# MIO_SD.net
KiCad netlist of a schematic drawn in Altium Designer
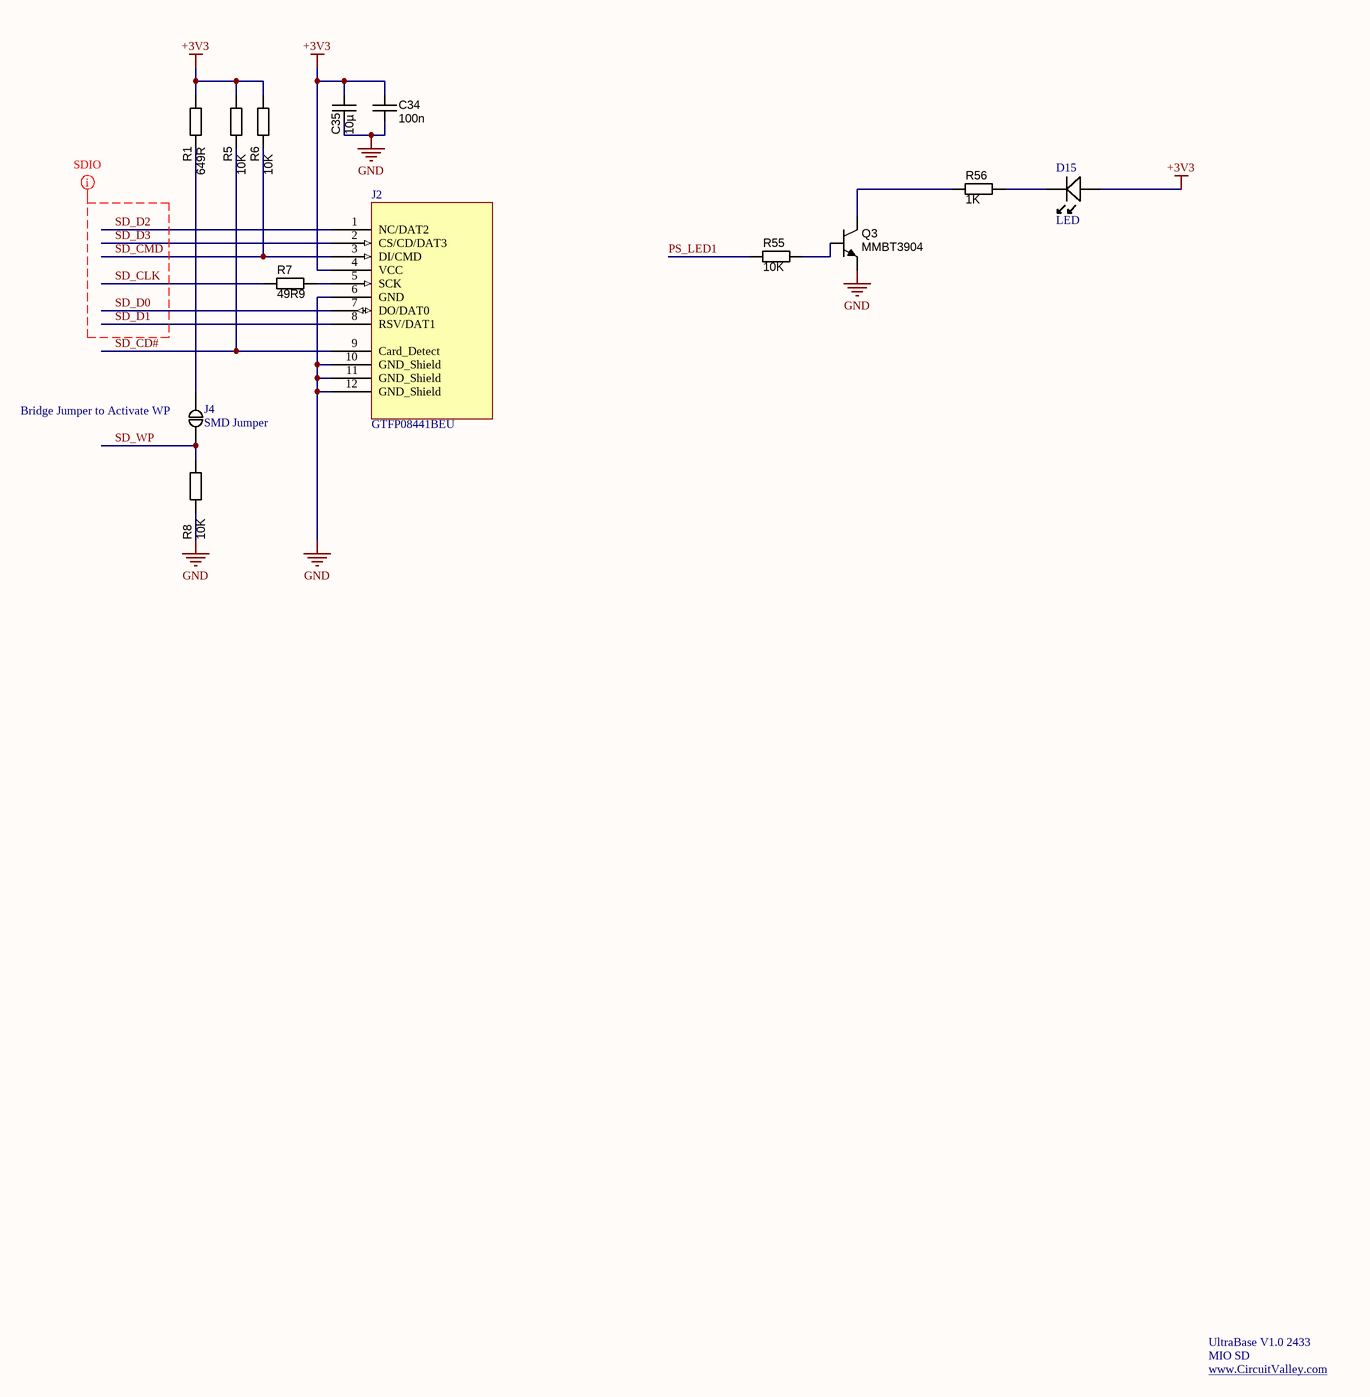
[diagram p0: MIO_SD.SchDoc]

(export (version "E")
  (design (tool "Eeschema 10.0.6"))
  (components
    (comp (ref "C34")
      (value "100n")
      (footprint "CAPC1608N")
      (description "Capacitor SMD Cer 1nF 10% 100V X7R 0603")
      (fields (field (name "TOLERANCE") "±10%"))
      (libsource (lib "PBL - Capacitors") (part "CAPC_1n_0603_100V"))
    )
    (comp (ref "C35")
      (value "10µ")
      (footprint "CAPC3225N")
      (description "Capacitor SMD Cer 10uF 20% 16V X5R 1210")
      (fields (field (name "TOLERANCE") "±20%"))
      (libsource (lib "PBL - Capacitors") (part "CAPC_10u_1210_50V"))
    )
    (comp (ref "D15") (value "LED") (footprint "1206_LED") (libsource (lib "cvlib") (part "LED")))
    (comp (ref "J2")
      (value "GTFP08441BEU")
      (footprint "GTFP08441BEU")
      (description "MicroSD card")
      (libsource (lib "cvlib") (part "GTFP08441BEU"))
    )
    (comp (ref "J4")
      (value "SMD Jumper")
      (footprint "SMD_Jumper")
      (libsource (lib "cvlib") (part "SMD_Jumper"))
    )
    (comp (ref "Q3")
      (value "NPN_MMBT3904")
      (footprint "SOT23-3")
      (description "Transistor SMD NPN 40V 0.2A 350mW SOT-23")
      (fields (field (name "MANUFACTURER PART NUMBER 1") "MMBT3904"))
      (libsource (lib "PBL - Transistors") (part "NPN_MMBT3904"))
    )
    (comp (ref "R1")
      (value "649R")
      (footprint "RESC1608N")
      (description "Resistor, SMD chip")
      (fields (field (name "TOLERANCE") "±5%") (field (name "Comment") "RES_NL_0603"))
      (libsource (lib "PBL - Resistors") (part "RES_NL_0603"))
    )
    (comp (ref "R5")
      (value "10K")
      (footprint "RESC1608N")
      (description "Resistor, SMD chip")
      (fields (field (name "TOLERANCE") "±5%") (field (name "Comment") "RES_NL_0603"))
      (libsource (lib "PBL - Resistors") (part "RES_NL_0603"))
    )
    (comp (ref "R6")
      (value "10K")
      (footprint "RESC1608N")
      (description "Resistor, SMD chip")
      (fields (field (name "TOLERANCE") "±5%") (field (name "Comment") "RES_NL_0603"))
      (libsource (lib "PBL - Resistors") (part "RES_NL_0603"))
    )
    (comp (ref "R7")
      (value "49R9")
      (footprint "RESC1608N")
      (description "Resistor, SMD chip")
      (fields (field (name "TOLERANCE") "±5%") (field (name "Comment") "RES_NL_0603"))
      (libsource (lib "") (part "RES_NL_0603_1"))
    )
    (comp (ref "R8")
      (value "10K")
      (footprint "RESC1608N")
      (description "Resistor, SMD chip")
      (fields (field (name "TOLERANCE") "±5%") (field (name "Comment") "RES_NL_0603"))
      (libsource (lib "PBL - Resistors") (part "RES_NL_0603"))
    )
    (comp (ref "R55")
      (value "10K")
      (footprint "RESC1608N")
      (description "Resistor, SMD chip")
      (fields (field (name "TOLERANCE") "±5%") (field (name "Comment") "RES_NL_0603"))
      (libsource (lib "") (part "RES_NL_0603_1"))
    )
    (comp (ref "R56")
      (value "1K")
      (footprint "RESC1608N")
      (description "Resistor, SMD chip")
      (fields (field (name "TOLERANCE") "±5%") (field (name "Comment") "RES_NL_0603"))
      (libsource (lib "") (part "RES_NL_0603_1"))
    )
  )
  (nets
    (net (code "1") (name "+3V3") (class "Default")
      (node (ref "C34") (pin "1") (pintype "passive"))
      (node (ref "C35") (pin "1") (pintype "passive"))
      (node (ref "D15") (pin "A") (pinfunction "A_A") (pintype "passive"))
      (node (ref "J2") (pin "4") (pinfunction "VCC_4") (pintype "power_in"))
      (node (ref "R1") (pin "1") (pinfunction "1_1") (pintype "passive"))
      (node (ref "R5") (pin "1") (pinfunction "1_1") (pintype "passive"))
      (node (ref "R6") (pin "1") (pinfunction "1_1") (pintype "passive"))
    )
    (net (code "2") (name "/PS_LED1") (class "Default")
      (node (ref "R55") (pin "1") (pinfunction "1_1") (pintype "passive"))
    )
    (net (code "3") (name "/SD_CD#") (class "Default")
      (node (ref "J2") (pin "9") (pinfunction "Card_Detect_9") (pintype "passive"))
      (node (ref "R5") (pin "2") (pinfunction "2_2") (pintype "passive"))
    )
    (net (code "4") (name "/SD_CLK") (class "Default")
      (node (ref "R7") (pin "1") (pinfunction "1_1") (pintype "passive"))
    )
    (net (code "5") (name "/SD_CMD") (class "Default")
      (node (ref "J2") (pin "3") (pinfunction "DI/CMD_3") (pintype "input"))
      (node (ref "R6") (pin "2") (pinfunction "2_2") (pintype "passive"))
    )
    (net (code "6") (name "/SD_D0") (class "Default")
      (node (ref "J2") (pin "7") (pinfunction "DO/DAT0_7") (pintype "bidirectional"))
    )
    (net (code "7") (name "/SD_D1") (class "Default")
      (node (ref "J2") (pin "8") (pinfunction "RSV/DAT1_8") (pintype "passive"))
    )
    (net (code "8") (name "/SD_D2") (class "Default")
      (node (ref "J2") (pin "1") (pinfunction "NC/DAT2_1") (pintype "passive"))
    )
    (net (code "9") (name "/SD_D3") (class "Default")
      (node (ref "J2") (pin "2") (pinfunction "CS/CD/DAT3_2") (pintype "input"))
    )
    (net (code "10") (name "/SD_WP") (class "Default")
      (node (ref "J4") (pin "1") (pinfunction "1_1") (pintype "passive"))
      (node (ref "R8") (pin "1") (pinfunction "1_1") (pintype "passive"))
    )
    (net (code "11") (name "GND") (class "Default")
      (node (ref "C34") (pin "2") (pintype "passive"))
      (node (ref "C35") (pin "2") (pintype "passive"))
      (node (ref "J2") (pin "10") (pinfunction "GND_Shield_10") (pintype "passive"))
      (node (ref "J2") (pin "11") (pinfunction "GND_Shield_11") (pintype "passive"))
      (node (ref "J2") (pin "12") (pinfunction "GND_Shield_12") (pintype "passive"))
      (node (ref "J2") (pin "6") (pinfunction "GND_6") (pintype "passive"))
      (node (ref "Q3") (pin "2") (pinfunction "E_2") (pintype "passive"))
      (node (ref "R8") (pin "2") (pinfunction "2_2") (pintype "passive"))
    )
    (net (code "12") (name "Net-(D15-PadK)") (class "Default")
      (node (ref "D15") (pin "K") (pinfunction "K_K") (pintype "passive"))
      (node (ref "R56") (pin "2") (pinfunction "2_2") (pintype "passive"))
    )
    (net (code "13") (name "Net-(J2-SCK)") (class "Default")
      (node (ref "J2") (pin "5") (pinfunction "SCK_5") (pintype "input"))
      (node (ref "R7") (pin "2") (pinfunction "2_2") (pintype "passive"))
    )
    (net (code "14") (name "Net-(J4-Pad2)") (class "Default")
      (node (ref "J4") (pin "2") (pinfunction "2_2") (pintype "passive"))
      (node (ref "R1") (pin "2") (pinfunction "2_2") (pintype "passive"))
    )
    (net (code "15") (name "Net-(Q3-B)") (class "Default")
      (node (ref "Q3") (pin "1") (pinfunction "B_1") (pintype "passive"))
      (node (ref "R55") (pin "2") (pinfunction "2_2") (pintype "passive"))
    )
    (net (code "16") (name "Net-(Q3-C)") (class "Default")
      (node (ref "Q3") (pin "3") (pinfunction "C_3") (pintype "passive"))
      (node (ref "R56") (pin "1") (pinfunction "1_1") (pintype "passive"))
    )
  )
)
